# CAMERA_CSI_RPIv2.net
KiCad netlist of a schematic drawn in Altium Designer
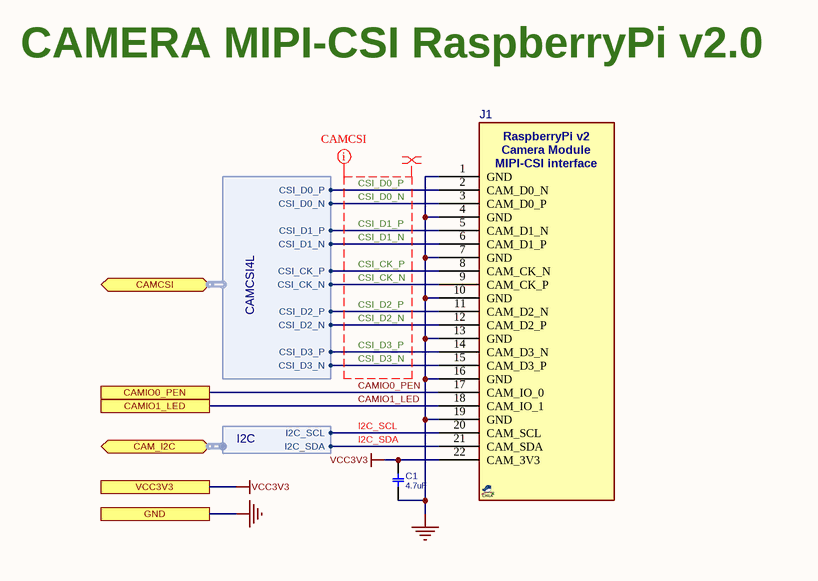
[diagram p0: CAMERA_CSI_RPIv2.SchDoc]

(export (version "E")
  (design (tool "Eeschema 10.0.6"))
  (components
    (comp (ref "C1")
      (value "4.7uF")
      (footprint "C0402")
      (description "CAP, MLCC")
      (fields (field (name "MANF_P#") "LMK105BBJ475MVLF") (field (name "MANF") "Taiyo Yuden"))
      (libsource (lib "passive_smd") (part "CAP_SMD_MLCC"))
    )
    (comp (ref "J1")
      (value "RPICAM_V2")
      (footprint "FPC50_22B")
      (description "Camera Module, Color, MIPI-CSI FPC22")
      (libsource (lib "camera") (part "RPICAM_V2_FPC22"))
    )
  )
  (nets
    (net (code "3") (name "/CAMIO0_PEN") (class "Default")
      (node (ref "J1") (pin "17") (pinfunction "CAM_IO_0_17") (pintype "passive"))
    )
    (net (code "4") (name "/CAMIO1_LED") (class "Default")
      (node (ref "J1") (pin "18") (pinfunction "CAM_IO_1_18") (pintype "passive"))
    )
    (net (code "5") (name "/CSI_CK_N") (class "Default")
      (node (ref "J1") (pin "9") (pinfunction "CAM_CK_P_9") (pintype "passive"))
    )
    (net (code "6") (name "/CSI_CK_P") (class "Default")
      (node (ref "J1") (pin "8") (pinfunction "CAM_CK_N_8") (pintype "passive"))
    )
    (net (code "7") (name "/CSI_D0_N") (class "Default")
      (node (ref "J1") (pin "3") (pinfunction "CAM_D0_P_3") (pintype "passive"))
    )
    (net (code "8") (name "/CSI_D0_P") (class "Default")
      (node (ref "J1") (pin "2") (pinfunction "CAM_D0_N_2") (pintype "passive"))
    )
    (net (code "9") (name "/CSI_D1_N") (class "Default")
      (node (ref "J1") (pin "6") (pinfunction "CAM_D1_P_6") (pintype "passive"))
    )
    (net (code "10") (name "/CSI_D1_P") (class "Default")
      (node (ref "J1") (pin "5") (pinfunction "CAM_D1_N_5") (pintype "passive"))
    )
    (net (code "11") (name "/CSI_D2_N") (class "Default")
      (node (ref "J1") (pin "12") (pinfunction "CAM_D2_P_12") (pintype "passive"))
    )
    (net (code "12") (name "/CSI_D2_P") (class "Default")
      (node (ref "J1") (pin "11") (pinfunction "CAM_D2_N_11") (pintype "passive"))
    )
    (net (code "13") (name "/CSI_D3_N") (class "Default")
      (node (ref "J1") (pin "15") (pinfunction "CAM_D3_P_15") (pintype "passive"))
    )
    (net (code "14") (name "/CSI_D3_P") (class "Default")
      (node (ref "J1") (pin "14") (pinfunction "CAM_D3_N_14") (pintype "passive"))
    )
    (net (code "15") (name "/I2C_SCL") (class "Default")
      (node (ref "J1") (pin "20") (pinfunction "CAM_SCL_20") (pintype "passive"))
    )
    (net (code "16") (name "/I2C_SDA") (class "Default")
      (node (ref "J1") (pin "21") (pinfunction "CAM_SDA_21") (pintype "passive"))
    )
    (net (code "19") (name "GND") (class "Default")
      (node (ref "C1") (pin "1") (pinfunction "1_1") (pintype "passive"))
      (node (ref "J1") (pin "1") (pinfunction "GND_1") (pintype "passive"))
      (node (ref "J1") (pin "10") (pinfunction "GND_10") (pintype "passive"))
      (node (ref "J1") (pin "13") (pinfunction "GND_13") (pintype "passive"))
      (node (ref "J1") (pin "16") (pinfunction "GND_16") (pintype "passive"))
      (node (ref "J1") (pin "19") (pinfunction "GND_19") (pintype "passive"))
      (node (ref "J1") (pin "4") (pinfunction "GND_4") (pintype "passive"))
      (node (ref "J1") (pin "7") (pinfunction "GND_7") (pintype "passive"))
    )
    (net (code "20") (name "VCC3V3") (class "Default")
      (node (ref "C1") (pin "2") (pinfunction "2_2") (pintype "passive"))
      (node (ref "J1") (pin "22") (pinfunction "CAM_3V3_22") (pintype "passive"))
    )
  )
)
